# 03_-_DAC.net
KiCad netlist of a schematic drawn in Altium Designer
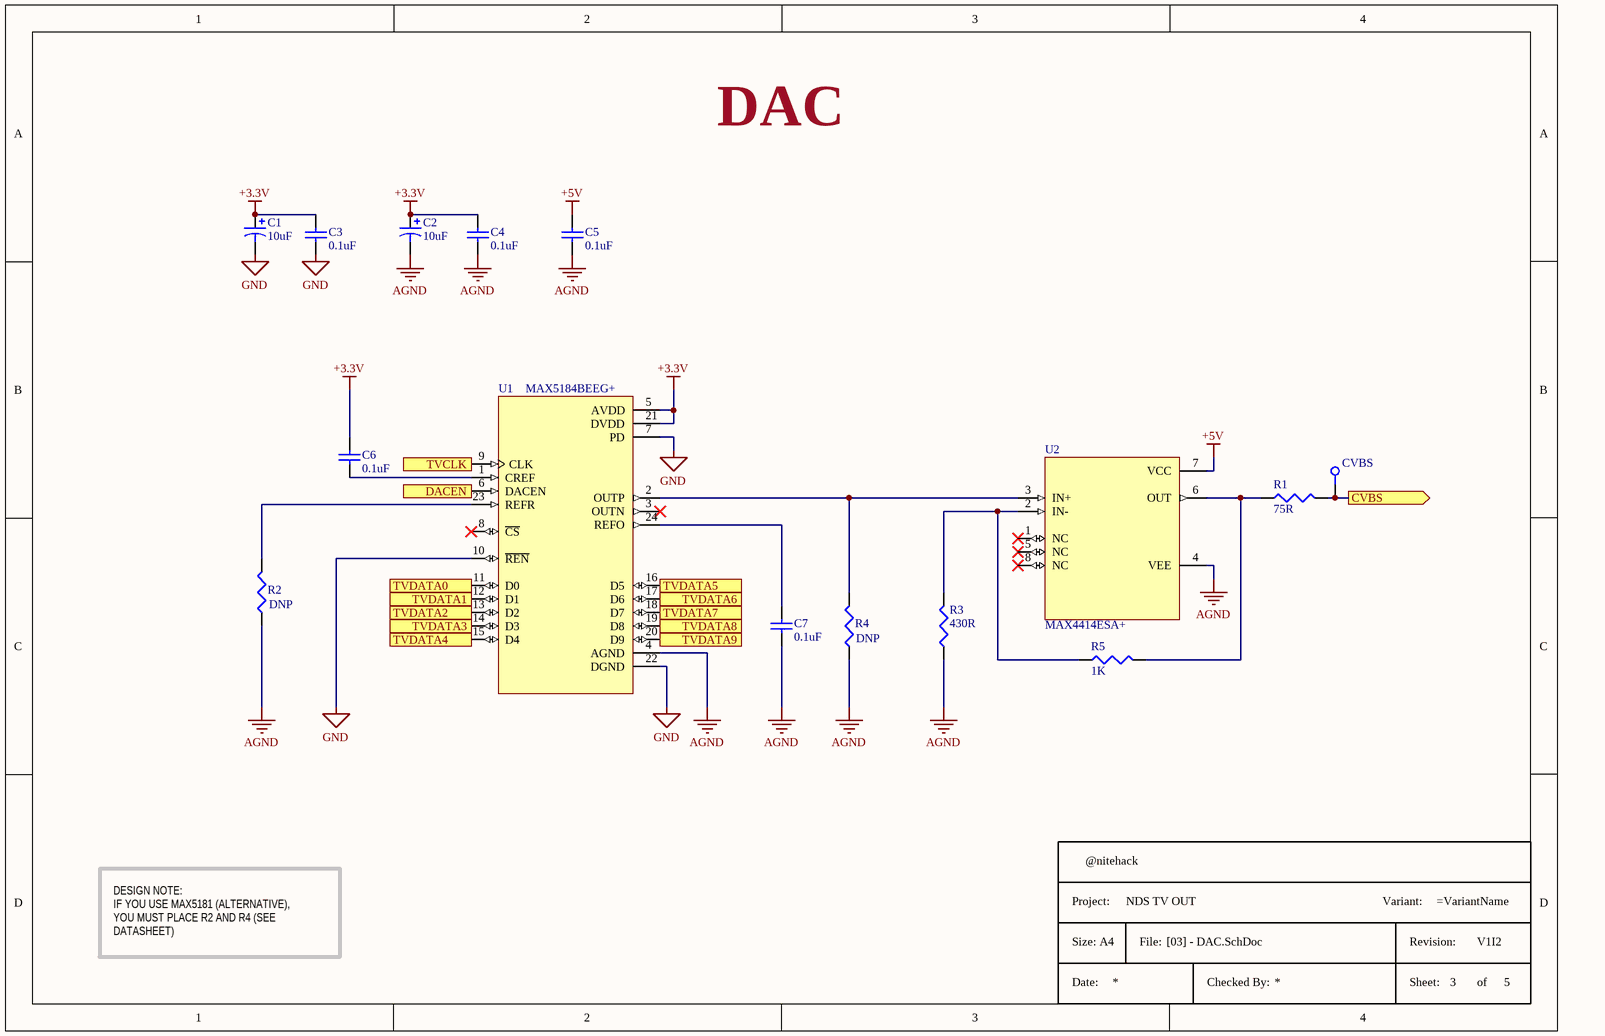
[diagram p0: [03] - DAC.SchDoc]

(export (version "E")
  (design (tool "Eeschema 10.0.6"))
  (components
    (comp (ref "C1")
      (value "10uF")
      (footprint "C1206T")
      (fields
        (field (name "MANUFACTURER") "KEMET")
        (field (name "MANUFACTURER PART NUMBER") "T491A106K010AT")
        (field (name "TOLERANCE") "10%")
      )
      (libsource (lib "SCHLIB") (part "T491A106K010AT"))
    )
    (comp (ref "C2")
      (value "10uF")
      (footprint "C1206T")
      (fields
        (field (name "MANUFACTURER") "KEMET")
        (field (name "MANUFACTURER PART NUMBER") "T491A106K010AT")
        (field (name "TOLERANCE") "10%")
      )
      (libsource (lib "SCHLIB") (part "T491A106K010AT"))
    )
    (comp (ref "C3")
      (value "0.1uF")
      (footprint "C1206")
      (description "MURATA - GRM319R71H104KA01D - COND, CERÁ MULT, X7R, 100NF, 50V, 1206")
      (fields
        (field (name "MANUFACTURER") "MURATA")
        (field (name "MANUFACTURER PART NUMBER") "GRM319R71H104KA01D")
      )
      (libsource (lib "SCHLIB") (part "GRM319R71H104KA01D"))
    )
    (comp (ref "C4")
      (value "0.1uF")
      (footprint "C1206")
      (description "MURATA - GRM319R71H104KA01D - COND, CERÁ MULT, X7R, 100NF, 50V, 1206")
      (fields
        (field (name "MANUFACTURER") "MURATA")
        (field (name "MANUFACTURER PART NUMBER") "GRM319R71H104KA01D")
      )
      (libsource (lib "SCHLIB") (part "GRM319R71H104KA01D"))
    )
    (comp (ref "C5")
      (value "0.1uF")
      (footprint "C1206")
      (description "MURATA - GRM319R71H104KA01D - COND, CERÁ MULT, X7R, 100NF, 50V, 1206")
      (fields
        (field (name "MANUFACTURER") "MURATA")
        (field (name "MANUFACTURER PART NUMBER") "GRM319R71H104KA01D")
      )
      (libsource (lib "SCHLIB") (part "GRM319R71H104KA01D"))
    )
    (comp (ref "C6")
      (value "0.1uF")
      (footprint "C1206")
      (description "MURATA - GRM319R71H104KA01D - COND, CERÁ MULT, X7R, 100NF, 50V, 1206")
      (fields
        (field (name "MANUFACTURER") "MURATA")
        (field (name "MANUFACTURER PART NUMBER") "GRM319R71H104KA01D")
      )
      (libsource (lib "SCHLIB") (part "GRM319R71H104KA01D"))
    )
    (comp (ref "C7")
      (value "0.1uF")
      (footprint "C1206")
      (description "MURATA - GRM319R71H104KA01D - COND, CERÁ MULT, X7R, 100NF, 50V, 1206")
      (fields
        (field (name "MANUFACTURER") "MURATA")
        (field (name "MANUFACTURER PART NUMBER") "GRM319R71H104KA01D")
      )
      (libsource (lib "SCHLIB") (part "GRM319R71H104KA01D"))
    )
    (comp (ref "CVBS")
      (value "TP_25MILC")
      (footprint "TP_25C")
      (description "Test Point 25mil")
      (libsource (lib "SCHLIB") (part "TP_25MILC"))
    )
    (comp (ref "R1")
      (value "75R")
      (footprint "R0603")
      (description "VISHAY - CRCW060375R0FKEA - RES, 75R, 1%, 0.1W, 0603, THICK FILM")
      (fields
        (field (name "MANUFACTURER") "Vishay")
        (field (name "MANUFACTURER PART NUMBER") "CRCW060375R0FKEA")
      )
      (libsource (lib "SCHLIB") (part "CRCW060375R0FKEA"))
    )
    (comp (ref "R2") (value "DNP") (footprint "R0603") (libsource (lib "SCHLIB") (part "R0603")))
    (comp (ref "R3")
      (value "430R")
      (footprint "R0603")
      (description "Res, 430R, 0.1%, 0.1W, 0603, Thin Film")
      (fields
        (field (name "MANUFACTURER") "Multicomp")
        (field (name "MANUFACTURER PART NUMBER") "MCWF06R4300BTL")
      )
      (libsource (lib "SCHLIB") (part "MCWF06R4300BTL"))
    )
    (comp (ref "R4") (value "DNP") (footprint "R0603") (libsource (lib "SCHLIB") (part "R0603")))
    (comp (ref "R5")
      (value "1K")
      (footprint "R0603")
      (fields
        (field (name "MANUFACTURER") "Rohm")
        (field (name "MANUFACTURER PART NUMBER") "ESR03EZPF1001")
        (field (name "TOLERANCE") "1%")
      )
      (libsource (lib "SCHLIB") (part "ESR03EZPF1001"))
    )
    (comp (ref "U1")
      (value "MAX5184BEEG+")
      (footprint "SOP63P602X175-24N")
      (description "DAC 1-CH Current Steering 10-bit 24-Pin QSOP")
      (fields (field (name "MANUFACTURER") "Maxim"))
      (libsource (lib "SCHLIB") (part "MAX5184BEEG+"))
    )
    (comp (ref "U2")
      (value "MAX4414ESA+")
      (footprint "SOIC127P600X175-8N")
      (description "IC OPAMP VFB 400MHZ RRO 8SOIC")
      (fields (field (name "MANUFACTURER") "Maxim"))
      (libsource (lib "SCHLIB") (part "MAX4414ESA+"))
    )
  )
  (nets
    (net (code "1") (name "+3.3V") (class "Default")
      (node (ref "C1") (pin "1") (pinfunction "1_1") (pintype "passive"))
      (node (ref "C2") (pin "1") (pinfunction "1_1") (pintype "passive"))
      (node (ref "C3") (pin "2") (pinfunction "2_2") (pintype "passive"))
      (node (ref "C4") (pin "2") (pinfunction "2_2") (pintype "passive"))
      (node (ref "C6") (pin "1") (pinfunction "1_1") (pintype "passive"))
      (node (ref "U1") (pin "21") (pinfunction "DVDD_21") (pintype "power_in"))
      (node (ref "U1") (pin "5") (pinfunction "AVDD_5") (pintype "power_in"))
    )
    (net (code "2") (name "+5V") (class "Default")
      (node (ref "C5") (pin "2") (pinfunction "2_2") (pintype "passive"))
      (node (ref "U2") (pin "7") (pinfunction "VCC_7") (pintype "power_in"))
    )
    (net (code "3") (name "/CVBS") (class "Default")
      (node (ref "CVBS") (pin "1") (pinfunction "1_1") (pintype "passive"))
      (node (ref "R1") (pin "2") (pinfunction "2_2") (pintype "passive"))
    )
    (net (code "4") (name "/DACEN") (class "Default")
      (node (ref "U1") (pin "6") (pinfunction "DACEN_6") (pintype "input"))
    )
    (net (code "5") (name "/TVCLK") (class "Default")
      (node (ref "U1") (pin "9") (pinfunction "CLK_9") (pintype "input"))
    )
    (net (code "6") (name "/TVDATA0") (class "Default")
      (node (ref "U1") (pin "11") (pinfunction "D0_11") (pintype "bidirectional"))
    )
    (net (code "7") (name "/TVDATA1") (class "Default")
      (node (ref "U1") (pin "12") (pinfunction "D1_12") (pintype "bidirectional"))
    )
    (net (code "8") (name "/TVDATA2") (class "Default")
      (node (ref "U1") (pin "13") (pinfunction "D2_13") (pintype "bidirectional"))
    )
    (net (code "9") (name "/TVDATA3") (class "Default")
      (node (ref "U1") (pin "14") (pinfunction "D3_14") (pintype "bidirectional"))
    )
    (net (code "10") (name "/TVDATA4") (class "Default")
      (node (ref "U1") (pin "15") (pinfunction "D4_15") (pintype "bidirectional"))
    )
    (net (code "11") (name "/TVDATA5") (class "Default")
      (node (ref "U1") (pin "16") (pinfunction "D5_16") (pintype "bidirectional"))
    )
    (net (code "12") (name "/TVDATA6") (class "Default")
      (node (ref "U1") (pin "17") (pinfunction "D6_17") (pintype "bidirectional"))
    )
    (net (code "13") (name "/TVDATA7") (class "Default")
      (node (ref "U1") (pin "18") (pinfunction "D7_18") (pintype "bidirectional"))
    )
    (net (code "14") (name "/TVDATA8") (class "Default")
      (node (ref "U1") (pin "19") (pinfunction "D8_19") (pintype "bidirectional"))
    )
    (net (code "15") (name "/TVDATA9") (class "Default")
      (node (ref "U1") (pin "20") (pinfunction "D9_20") (pintype "bidirectional"))
    )
    (net (code "16") (name "AGND") (class "Default")
      (node (ref "C2") (pin "2") (pinfunction "2_2") (pintype "passive"))
      (node (ref "C4") (pin "1") (pinfunction "1_1") (pintype "passive"))
      (node (ref "C5") (pin "1") (pinfunction "1_1") (pintype "passive"))
      (node (ref "C7") (pin "1") (pinfunction "1_1") (pintype "passive"))
      (node (ref "R2") (pin "1") (pinfunction "1_1") (pintype "passive"))
      (node (ref "R3") (pin "1") (pinfunction "1_1") (pintype "passive"))
      (node (ref "R4") (pin "1") (pinfunction "1_1") (pintype "passive"))
      (node (ref "U1") (pin "4") (pinfunction "AGND_4") (pintype "power_in"))
      (node (ref "U2") (pin "4") (pinfunction "VEE_4") (pintype "power_in"))
    )
    (net (code "17") (name "GND") (class "Default")
      (node (ref "C1") (pin "2") (pinfunction "2_2") (pintype "passive"))
      (node (ref "C3") (pin "1") (pinfunction "1_1") (pintype "passive"))
      (node (ref "U1") (pin "10") (pinfunction "~{REN}_10") (pintype "bidirectional"))
      (node (ref "U1") (pin "22") (pinfunction "DGND_22") (pintype "power_in"))
      (node (ref "U1") (pin "7") (pinfunction "PD_7") (pintype "power_in"))
    )
    (net (code "18") (name "Net-(U1-CREF)") (class "Default")
      (node (ref "C6") (pin "2") (pinfunction "2_2") (pintype "passive"))
      (node (ref "U1") (pin "1") (pinfunction "CREF_1") (pintype "input"))
    )
    (net (code "19") (name "Net-(U1-OUTP)") (class "Default")
      (node (ref "R4") (pin "2") (pinfunction "2_2") (pintype "passive"))
      (node (ref "U1") (pin "2") (pinfunction "OUTP_2") (pintype "output"))
      (node (ref "U2") (pin "3") (pinfunction "IN+_3") (pintype "input"))
    )
    (net (code "20") (name "Net-(U1-REFO)") (class "Default")
      (node (ref "C7") (pin "2") (pinfunction "2_2") (pintype "passive"))
      (node (ref "U1") (pin "24") (pinfunction "REFO_24") (pintype "output"))
    )
    (net (code "21") (name "Net-(U1-REFR)") (class "Default")
      (node (ref "R2") (pin "2") (pinfunction "2_2") (pintype "passive"))
      (node (ref "U1") (pin "23") (pinfunction "REFR_23") (pintype "input"))
    )
    (net (code "22") (name "Net-(U2-IN-)") (class "Default")
      (node (ref "R3") (pin "2") (pinfunction "2_2") (pintype "passive"))
      (node (ref "R5") (pin "1") (pinfunction "1_1") (pintype "passive"))
      (node (ref "U2") (pin "2") (pinfunction "IN-_2") (pintype "input"))
    )
    (net (code "23") (name "Net-(U2-OUT)") (class "Default")
      (node (ref "R1") (pin "1") (pinfunction "1_1") (pintype "passive"))
      (node (ref "R5") (pin "2") (pinfunction "2_2") (pintype "passive"))
      (node (ref "U2") (pin "6") (pinfunction "OUT_6") (pintype "output"))
    )
    (net (code "24") (name "unconnected-(U1-OUTN-Pad3)") (class "Default")
      (node (ref "U1") (pin "3") (pinfunction "OUTN_3") (pintype "output+no_connect"))
    )
    (net (code "25") (name "unconnected-(U1-~{CS}-Pad8)") (class "Default")
      (node (ref "U1") (pin "8") (pinfunction "~{CS}_8") (pintype "bidirectional+no_connect"))
    )
    (net (code "26") (name "unconnected-(U2-NC-Pad1)") (class "Default")
      (node (ref "U2") (pin "1") (pinfunction "NC_1") (pintype "bidirectional+no_connect"))
    )
    (net (code "27") (name "unconnected-(U2-NC-Pad5)") (class "Default")
      (node (ref "U2") (pin "5") (pinfunction "NC_5") (pintype "bidirectional+no_connect"))
    )
    (net (code "28") (name "unconnected-(U2-NC-Pad8)") (class "Default")
      (node (ref "U2") (pin "8") (pinfunction "NC_8") (pintype "bidirectional+no_connect"))
    )
  )
)
